# esp_tiny2.net
KiCad netlist of a schematic drawn in EAGLE
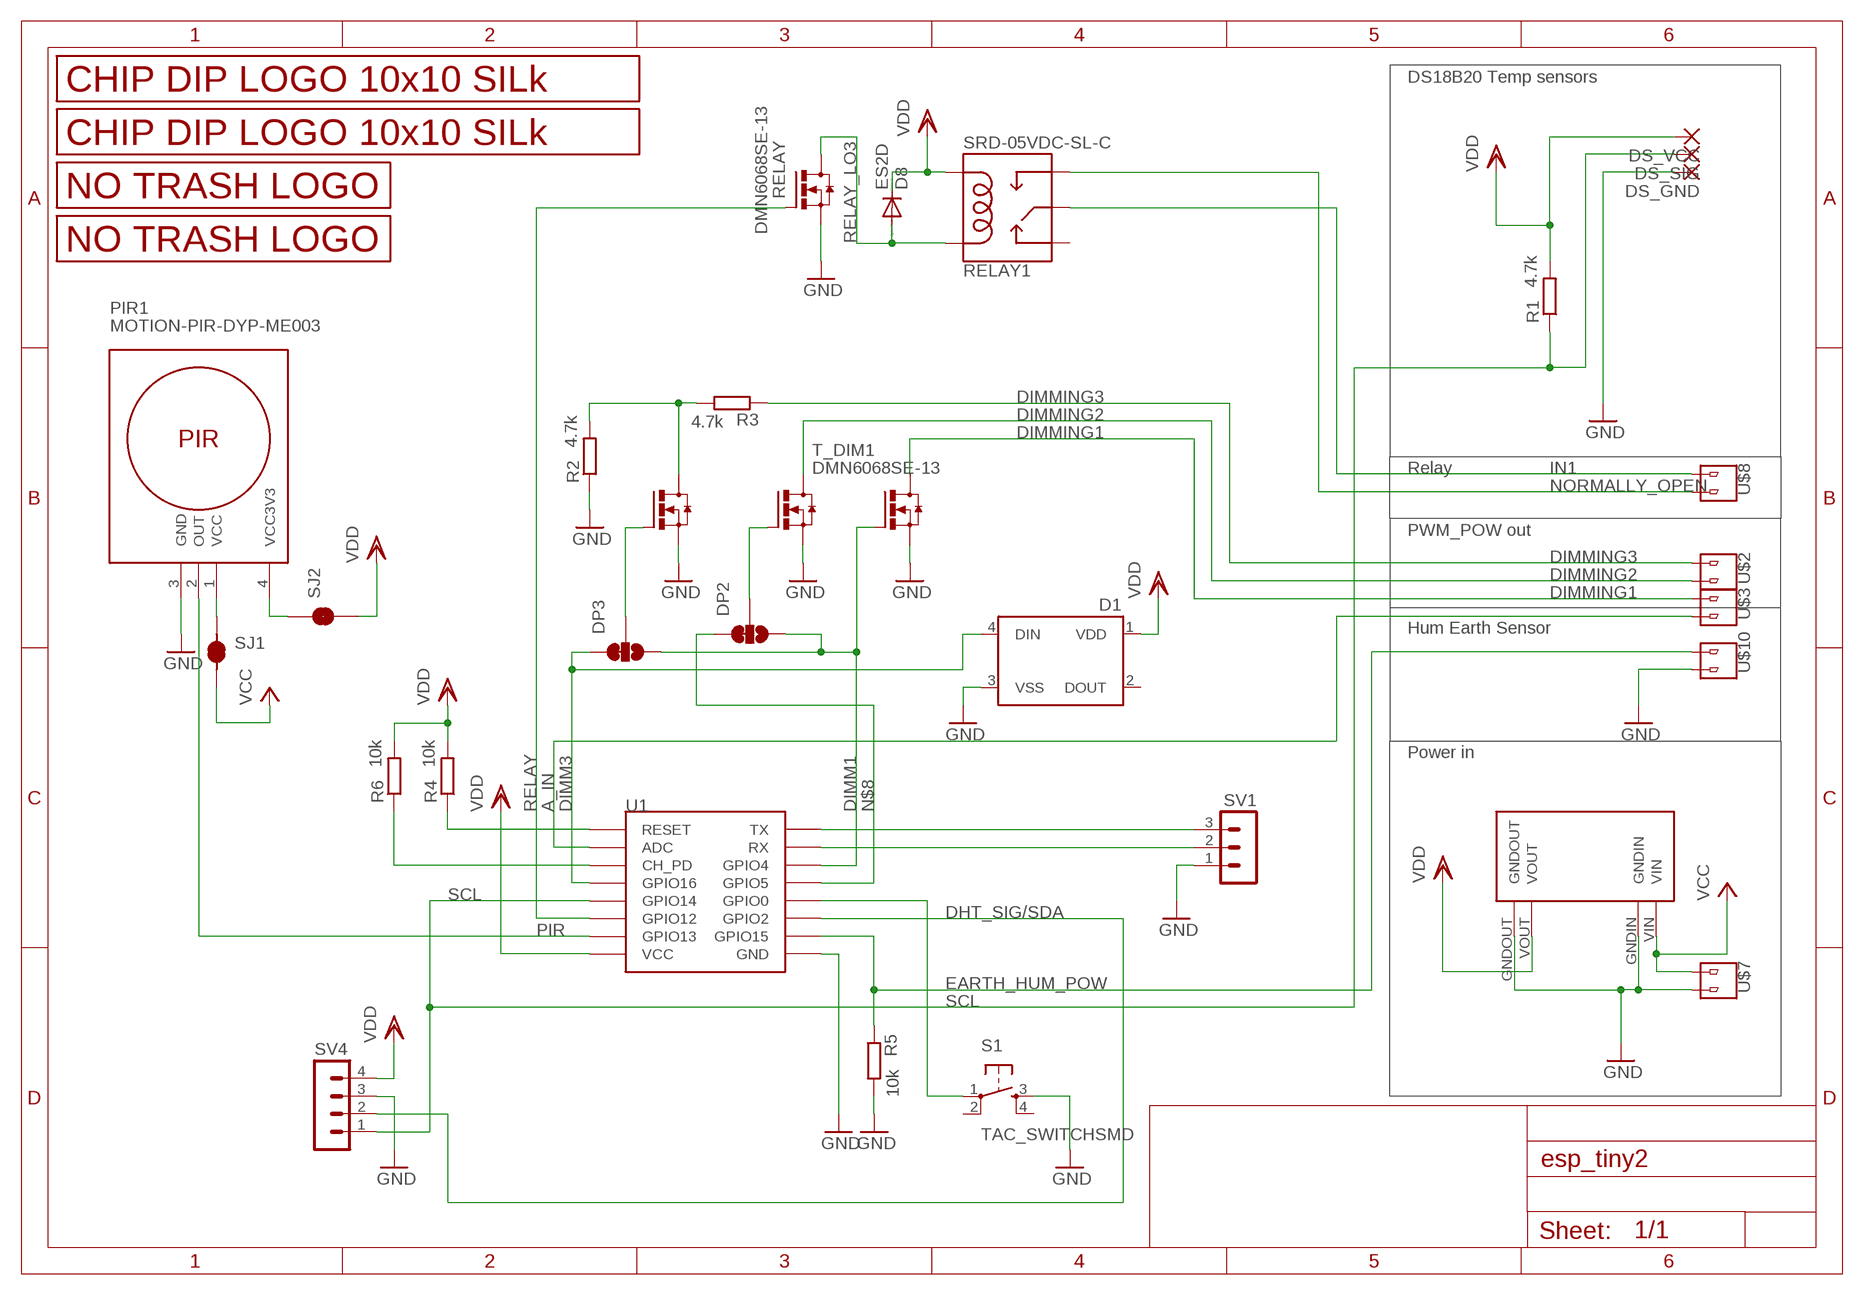
[diagram p0: schematic, sheet 1]

(export (version "E")
  (design (tool "Eeschema 10.0.6"))
  (components
    (comp (ref "D1")
      (value "WS2812B")
      (footprint "eagle-import:WS2812B")
      (libsource (lib "eagle-import") (part "WS2812B"))
    )
    (comp (ref "D8")
      (value "ES2D")
      (footprint "eagle-import:SMB")
      (libsource (lib "eagle-import") (part "DIODE-SMB"))
    )
    (comp (ref "DP2")
      (value "SMD_SJ_3WAY_CLOSED")
      (footprint "eagle-import:SMD_SJ_3WAY_CLOSED")
      (libsource (lib "eagle-import") (part "SMD_SJ_3WAY_CLOSED"))
    )
    (comp (ref "DP3")
      (value "SMD_SJ_3WAY_CLOSED")
      (footprint "eagle-import:SMD_SJ_3WAY_CLOSED")
      (libsource (lib "eagle-import") (part "SMD_SJ_3WAY_CLOSED"))
    )
    (comp (ref "DS_GND")
      (value "SMD2")
      (footprint "eagle-import:SMD1,27-2,54")
      (libsource (lib "eagle-import") (part "SMD2"))
    )
    (comp (ref "DS_SIG")
      (value "SMD2")
      (footprint "eagle-import:SMD1,27-2,54")
      (libsource (lib "eagle-import") (part "SMD2"))
    )
    (comp (ref "DS_VCC")
      (value "SMD2")
      (footprint "eagle-import:SMD1,27-2,54")
      (libsource (lib "eagle-import") (part "SMD2"))
    )
    (comp (ref "PIR1")
      (value "MOTION-PIR-DYP-ME003")
      (footprint "eagle-import:MOTION-PIR-DYP-ME003_FRAMELESS")
      (libsource (lib "eagle-import") (part "MOTION-PIR-DYP-ME003"))
    )
    (comp (ref "R1")
      (value "4.7k")
      (footprint "eagle-import:M0805")
      (libsource (lib "eagle-import") (part "R-EU_M0805"))
    )
    (comp (ref "R2")
      (value "4.7k")
      (footprint "eagle-import:M0805")
      (libsource (lib "eagle-import") (part "R-EU_M0805"))
    )
    (comp (ref "R3")
      (value "4.7k")
      (footprint "eagle-import:M0805")
      (libsource (lib "eagle-import") (part "R-EU_M0805"))
    )
    (comp (ref "R4")
      (value "10k")
      (footprint "eagle-import:M0805")
      (libsource (lib "eagle-import") (part "R-EU_M0805"))
    )
    (comp (ref "R5")
      (value "10k")
      (footprint "eagle-import:M0805")
      (libsource (lib "eagle-import") (part "R-EU_M0805"))
    )
    (comp (ref "R6")
      (value "10k")
      (footprint "eagle-import:M0805")
      (libsource (lib "eagle-import") (part "R-EU_M0805"))
    )
    (comp (ref "RELAY")
      (value "DMN6068SE-13")
      (footprint "eagle-import:SOT223")
      (libsource (lib "eagle-import") (part "NMOSFET_SMD_223"))
    )
    (comp (ref "RELAY1")
      (value "SRD-05VDC-SL-C")
      (footprint "eagle-import:SRD-05VDC-SL-C")
      (libsource (lib "eagle-import") (part "RELAYPTH"))
    )
    (comp (ref "S1")
      (value "TAC_SWITCHSMD")
      (footprint "eagle-import:TACTILE-SWITCH-SMD")
      (libsource (lib "eagle-import") (part "TAC_SWITCHSMD"))
    )
    (comp (ref "SJ1")
      (value "SMD_SJ_2WAY_CLOSEDCLOSED")
      (footprint "eagle-import:SMD_SJ_2WAY_CLOSED")
      (libsource (lib "eagle-import") (part "SMD_SJ_2WAY_CLOSEDCLOSED"))
    )
    (comp (ref "SJ2")
      (value "SMD_SJ_2WAY_OPEN")
      (footprint "eagle-import:SMD_SJ_2WAY_OPEN")
      (libsource (lib "eagle-import") (part "SMD_SJ_2WAY_OPEN"))
    )
    (comp (ref "SV1")
      (value "MA03-1")
      (footprint "eagle-import:MA03-1")
      (libsource (lib "eagle-import") (part "MA03-1"))
    )
    (comp (ref "SV4")
      (value "MA04-1")
      (footprint "eagle-import:MA04-1")
      (libsource (lib "eagle-import") (part "MA04-1"))
    )
    (comp (ref "T_DIM1")
      (value "DMN6068SE-13")
      (footprint "eagle-import:SOT223")
      (libsource (lib "eagle-import") (part "NMOSFET_SMD_223"))
    )
    (comp (ref "T_DIM2")
      (value "DMN6068SE-13")
      (footprint "eagle-import:SOT223")
      (libsource (lib "eagle-import") (part "NMOSFET_SMD_223"))
    )
    (comp (ref "T_DIM3")
      (value "DMN6068SE-13")
      (footprint "eagle-import:SOT223")
      (libsource (lib "eagle-import") (part "NMOSFET_SMD_223"))
    )
    (comp (ref "U$1")
      (value "LOGO_10X10_SILK")
      (footprint "eagle-import:LOGO2_10X10_SILK")
      (libsource (lib "eagle-import") (part "LOGO_10X10_SILK"))
    )
    (comp (ref "U$2")
      (value "V1")
      (footprint "eagle-import:2_SCREW_PIN")
      (libsource (lib "eagle-import") (part "2_PIN_CONNECTOR"))
    )
    (comp (ref "U$3")
      (value "V1")
      (footprint "eagle-import:2_SCREW_PIN")
      (libsource (lib "eagle-import") (part "2_PIN_CONNECTOR"))
    )
    (comp (ref "U$4")
      (value "LOGO_NO_TRASHNO_TRASH")
      (footprint "eagle-import:LOGO_ROHS_NO_TRASH")
      (libsource (lib "eagle-import") (part "LOGO_NO_TRASHNO_TRASH"))
    )
    (comp (ref "U$7")
      (value "V1")
      (footprint "eagle-import:2_SCREW_PIN")
      (libsource (lib "eagle-import") (part "2_PIN_CONNECTOR"))
    )
    (comp (ref "U$8")
      (value "V1")
      (footprint "eagle-import:2_SCREW_PIN")
      (libsource (lib "eagle-import") (part "2_PIN_CONNECTOR"))
    )
    (comp (ref "U$9")
      (value "LOGO_NO_TRASHROHS")
      (footprint "eagle-import:LOGO_ROHS_SYM")
      (libsource (lib "eagle-import") (part "LOGO_NO_TRASHROHS"))
    )
    (comp (ref "U$10")
      (value "V1")
      (footprint "eagle-import:2_SCREW_PIN")
      (libsource (lib "eagle-import") (part "2_PIN_CONNECTOR"))
    )
    (comp (ref "U$11")
      (value "LOGO_10X10_SILK")
      (footprint "eagle-import:LOGO2_10X10_SILK")
      (libsource (lib "eagle-import") (part "LOGO_10X10_SILK"))
    )
    (comp (ref "U$12")
      (value "MP1584EN")
      (footprint "eagle-import:MP1584EN")
      (libsource (lib "eagle-import") (part "MP1584EN"))
    )
    (comp (ref "U1")
      (value "ESP12SMD")
      (footprint "eagle-import:ESP12-SMD")
      (libsource (lib "eagle-import") (part "ESP12SMD"))
    )
  )
  (nets
    (net (code "1") (name "/A_IN") (class "Default")
      (node (ref "U$3") (pin "P$2") (pinfunction "2_P$2") (pintype "passive"))
      (node (ref "U1") (pin "ADC") (pinfunction "ADC_ADC") (pintype "bidirectional"))
    )
    (net (code "2") (name "/DHT_SIG{slash}SDA") (class "Default")
      (node (ref "SV4") (pin "2") (pinfunction "2_2") (pintype "passive"))
      (node (ref "U1") (pin "GPIO2") (pinfunction "GPIO2_GPIO2") (pintype "bidirectional"))
    )
    (net (code "3") (name "/DIMM1") (class "Default")
      (node (ref "DP2") (pin "3") (pinfunction "3_3") (pintype "passive"))
      (node (ref "DP3") (pin "3") (pinfunction "3_3") (pintype "passive"))
      (node (ref "T_DIM1") (pin "1") (pinfunction "G_1") (pintype "passive"))
      (node (ref "U1") (pin "GPIO4") (pinfunction "GPIO4_GPIO4") (pintype "bidirectional"))
    )
    (net (code "4") (name "/DIMM3") (class "Default")
      (node (ref "D1") (pin "4") (pinfunction "DIN_4") (pintype "input"))
      (node (ref "DP3") (pin "1") (pinfunction "1_1") (pintype "passive"))
      (node (ref "U1") (pin "GPIO16") (pinfunction "GPIO16_GPIO16") (pintype "bidirectional"))
    )
    (net (code "5") (name "/DIMMING1") (class "Default")
      (node (ref "T_DIM1") (pin "2") (pinfunction "D_2") (pintype "passive"))
      (node (ref "T_DIM1") (pin "4") (pinfunction "D_4") (pintype "passive"))
      (node (ref "U$3") (pin "P$1") (pinfunction "1_P$1") (pintype "passive"))
    )
    (net (code "6") (name "/DIMMING2") (class "Default")
      (node (ref "T_DIM2") (pin "2") (pinfunction "D_2") (pintype "passive"))
      (node (ref "T_DIM2") (pin "4") (pinfunction "D_4") (pintype "passive"))
      (node (ref "U$2") (pin "P$2") (pinfunction "2_P$2") (pintype "passive"))
    )
    (net (code "7") (name "/DIMMING3") (class "Default")
      (node (ref "R3") (pin "1") (pinfunction "1_1") (pintype "passive"))
      (node (ref "U$2") (pin "P$1") (pinfunction "1_P$1") (pintype "passive"))
    )
    (net (code "8") (name "/EARTH_HUM_POW") (class "Default")
      (node (ref "R5") (pin "1") (pinfunction "1_1") (pintype "passive"))
      (node (ref "U$10") (pin "P$1") (pinfunction "1_P$1") (pintype "passive"))
      (node (ref "U1") (pin "GPIO15") (pinfunction "GPIO15_GPIO15") (pintype "bidirectional"))
    )
    (net (code "9") (name "/IN1") (class "Default")
      (node (ref "RELAY1") (pin "SWCOMMON") (pinfunction "SWCOMMON_SWCOMMON") (pintype "bidirectional"))
      (node (ref "U$8") (pin "P$1") (pinfunction "1_P$1") (pintype "passive"))
    )
    (net (code "10") (name "/N$8") (class "Default")
      (node (ref "DP2") (pin "1") (pinfunction "1_1") (pintype "passive"))
      (node (ref "U1") (pin "GPIO5") (pinfunction "GPIO5_GPIO5") (pintype "bidirectional"))
    )
    (net (code "11") (name "/NORMALLY_OPEN") (class "Default")
      (node (ref "RELAY1") (pin "SWOPEN") (pinfunction "SWOPEN_SWOPEN") (pintype "bidirectional"))
      (node (ref "U$8") (pin "P$2") (pinfunction "2_P$2") (pintype "passive"))
    )
    (net (code "12") (name "/PIR") (class "Default")
      (node (ref "PIR1") (pin "2") (pinfunction "OUT_2") (pintype "output"))
      (node (ref "U1") (pin "GPIO13") (pinfunction "GPIO13_GPIO13") (pintype "bidirectional"))
    )
    (net (code "13") (name "/RELAY") (class "Default")
      (node (ref "RELAY") (pin "1") (pinfunction "G_1") (pintype "passive"))
      (node (ref "U1") (pin "GPIO12") (pinfunction "GPIO12_GPIO12") (pintype "bidirectional"))
    )
    (net (code "14") (name "/RELAY_LO3") (class "Default")
      (node (ref "D8") (pin "A") (pinfunction "A_A") (pintype "passive"))
      (node (ref "RELAY") (pin "2") (pinfunction "D_2") (pintype "passive"))
      (node (ref "RELAY") (pin "4") (pinfunction "D_4") (pintype "passive"))
      (node (ref "RELAY1") (pin "COIL1") (pinfunction "COIL1_COIL1") (pintype "bidirectional"))
    )
    (net (code "15") (name "/SCL") (class "Default")
      (node (ref "DS_SIG") (pin "1") (pinfunction "P_1") (pintype "passive"))
      (node (ref "R1") (pin "1") (pinfunction "1_1") (pintype "passive"))
      (node (ref "SV4") (pin "1") (pinfunction "1_1") (pintype "passive"))
      (node (ref "U1") (pin "GPIO14") (pinfunction "GPIO14_GPIO14") (pintype "bidirectional"))
    )
    (net (code "16") (name "GND") (class "Default")
      (node (ref "D1") (pin "3") (pinfunction "VSS_3") (pintype "power_in"))
      (node (ref "DS_GND") (pin "1") (pinfunction "P_1") (pintype "passive"))
      (node (ref "PIR1") (pin "3") (pinfunction "GND_3") (pintype "power_in"))
      (node (ref "R2") (pin "1") (pinfunction "1_1") (pintype "passive"))
      (node (ref "R5") (pin "2") (pinfunction "2_2") (pintype "passive"))
      (node (ref "RELAY") (pin "3") (pinfunction "S_3") (pintype "passive"))
      (node (ref "S1") (pin "3") (pinfunction "3_3") (pintype "passive"))
      (node (ref "SV1") (pin "1") (pinfunction "1_1") (pintype "passive"))
      (node (ref "SV4") (pin "3") (pinfunction "3_3") (pintype "passive"))
      (node (ref "T_DIM1") (pin "3") (pinfunction "S_3") (pintype "passive"))
      (node (ref "T_DIM2") (pin "3") (pinfunction "S_3") (pintype "passive"))
      (node (ref "T_DIM3") (pin "3") (pinfunction "S_3") (pintype "passive"))
      (node (ref "U$10") (pin "P$2") (pinfunction "2_P$2") (pintype "passive"))
      (node (ref "U$12") (pin "GNDIN") (pinfunction "GNDIN_GNDIN") (pintype "power_in"))
      (node (ref "U$12") (pin "GNDOUT") (pinfunction "GNDOUT_GNDOUT") (pintype "power_in"))
      (node (ref "U$7") (pin "P$2") (pinfunction "2_P$2") (pintype "passive"))
      (node (ref "U1") (pin "GND") (pinfunction "GND_GND") (pintype "bidirectional"))
    )
    (net (code "17") (name "Net-(PIR1-VCC)") (class "Default")
      (node (ref "PIR1") (pin "1") (pinfunction "VCC_1") (pintype "power_in"))
      (node (ref "SJ1") (pin "1") (pinfunction "1_1") (pintype "passive"))
    )
    (net (code "18") (name "Net-(PIR1-VCC3V3)") (class "Default")
      (node (ref "PIR1") (pin "4") (pinfunction "VCC3V3_4") (pintype "power_in"))
      (node (ref "SJ2") (pin "1") (pinfunction "1_1") (pintype "passive"))
    )
    (net (code "19") (name "Net-(R2-Pad2)") (class "Default")
      (node (ref "R2") (pin "2") (pinfunction "2_2") (pintype "passive"))
      (node (ref "R3") (pin "2") (pinfunction "2_2") (pintype "passive"))
      (node (ref "T_DIM3") (pin "2") (pinfunction "D_2") (pintype "passive"))
      (node (ref "T_DIM3") (pin "4") (pinfunction "D_4") (pintype "passive"))
    )
    (net (code "20") (name "Net-(R4-Pad1)") (class "Default")
      (node (ref "R4") (pin "1") (pinfunction "1_1") (pintype "passive"))
      (node (ref "U1") (pin "RESET") (pinfunction "RESET_RESET") (pintype "bidirectional"))
    )
    (net (code "21") (name "Net-(R6-Pad1)") (class "Default")
      (node (ref "R6") (pin "1") (pinfunction "1_1") (pintype "passive"))
      (node (ref "U1") (pin "CH_PD") (pinfunction "CH_PD_CH_PD") (pintype "bidirectional"))
    )
    (net (code "22") (name "Net-(S1-Pad1)") (class "Default")
      (node (ref "S1") (pin "1") (pinfunction "1_1") (pintype "passive"))
      (node (ref "U1") (pin "GPIO0") (pinfunction "GPIO0_GPIO0") (pintype "bidirectional"))
    )
    (net (code "23") (name "Net-(T_DIM2-G)") (class "Default")
      (node (ref "DP2") (pin "2") (pinfunction "2_2") (pintype "passive"))
      (node (ref "T_DIM2") (pin "1") (pinfunction "G_1") (pintype "passive"))
    )
    (net (code "24") (name "Net-(T_DIM3-G)") (class "Default")
      (node (ref "DP3") (pin "2") (pinfunction "2_2") (pintype "passive"))
      (node (ref "T_DIM3") (pin "1") (pinfunction "G_1") (pintype "passive"))
    )
    (net (code "25") (name "Net-(U1-RX)") (class "Default")
      (node (ref "SV1") (pin "2") (pinfunction "2_2") (pintype "passive"))
      (node (ref "U1") (pin "RXD0") (pinfunction "RX_RXD0") (pintype "bidirectional"))
    )
    (net (code "26") (name "Net-(U1-TX)") (class "Default")
      (node (ref "SV1") (pin "3") (pinfunction "3_3") (pintype "passive"))
      (node (ref "U1") (pin "TXD0") (pinfunction "TX_TXD0") (pintype "bidirectional"))
    )
    (net (code "27") (name "VCC") (class "Default")
      (node (ref "SJ1") (pin "3") (pinfunction "3_3") (pintype "passive"))
      (node (ref "U$12") (pin "VIN") (pinfunction "VIN_VIN") (pintype "power_in"))
      (node (ref "U$7") (pin "P$1") (pinfunction "1_P$1") (pintype "passive"))
    )
    (net (code "28") (name "VDD") (class "Default")
      (node (ref "D1") (pin "1") (pinfunction "VDD_1") (pintype "power_in"))
      (node (ref "D8") (pin "C") (pinfunction "C_C") (pintype "passive"))
      (node (ref "DS_VCC") (pin "1") (pinfunction "P_1") (pintype "passive"))
      (node (ref "R1") (pin "2") (pinfunction "2_2") (pintype "passive"))
      (node (ref "R4") (pin "2") (pinfunction "2_2") (pintype "passive"))
      (node (ref "R6") (pin "2") (pinfunction "2_2") (pintype "passive"))
      (node (ref "RELAY1") (pin "COIL0") (pinfunction "COIL0_COIL0") (pintype "bidirectional"))
      (node (ref "SJ2") (pin "3") (pinfunction "3_3") (pintype "passive"))
      (node (ref "SV4") (pin "4") (pinfunction "4_4") (pintype "passive"))
      (node (ref "U$12") (pin "VOUT") (pinfunction "VOUT_VOUT") (pintype "power_in"))
      (node (ref "U1") (pin "VCC") (pinfunction "VCC_VCC") (pintype "bidirectional"))
    )
    (net (code "29") (name "unconnected-(D1-DOUT-Pad2)") (class "Default")
      (node (ref "D1") (pin "2") (pinfunction "DOUT_2") (pintype "output"))
    )
    (net (code "30") (name "unconnected-(RELAY1-SWCLOSE-PadSWCLOSED)") (class "Default")
      (node (ref "RELAY1") (pin "SWCLOSED") (pinfunction "SWCLOSE_SWCLOSED") (pintype "bidirectional"))
    )
    (net (code "31") (name "unconnected-(S1-Pad2)") (class "Default")
      (node (ref "S1") (pin "2") (pinfunction "2_2") (pintype "passive"))
    )
    (net (code "32") (name "unconnected-(S1-Pad4)") (class "Default")
      (node (ref "S1") (pin "4") (pinfunction "4_4") (pintype "passive"))
    )
  )
)
